# switch_v2.net
KiCad netlist of a schematic drawn in EAGLE
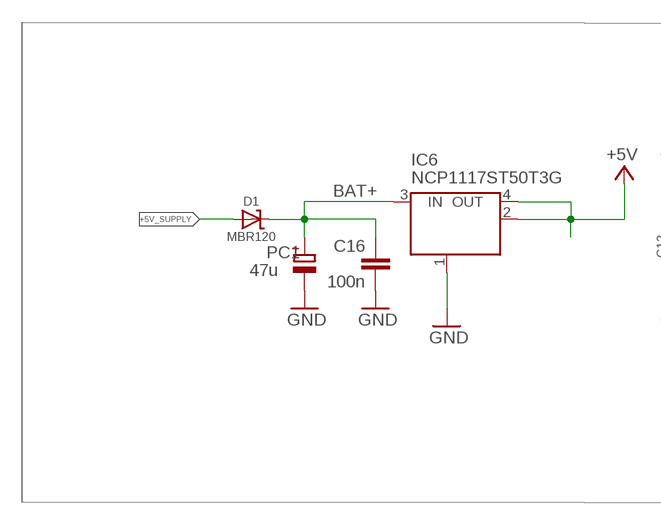
[diagram p0: schematic, sheet 1, part 1 of 2]
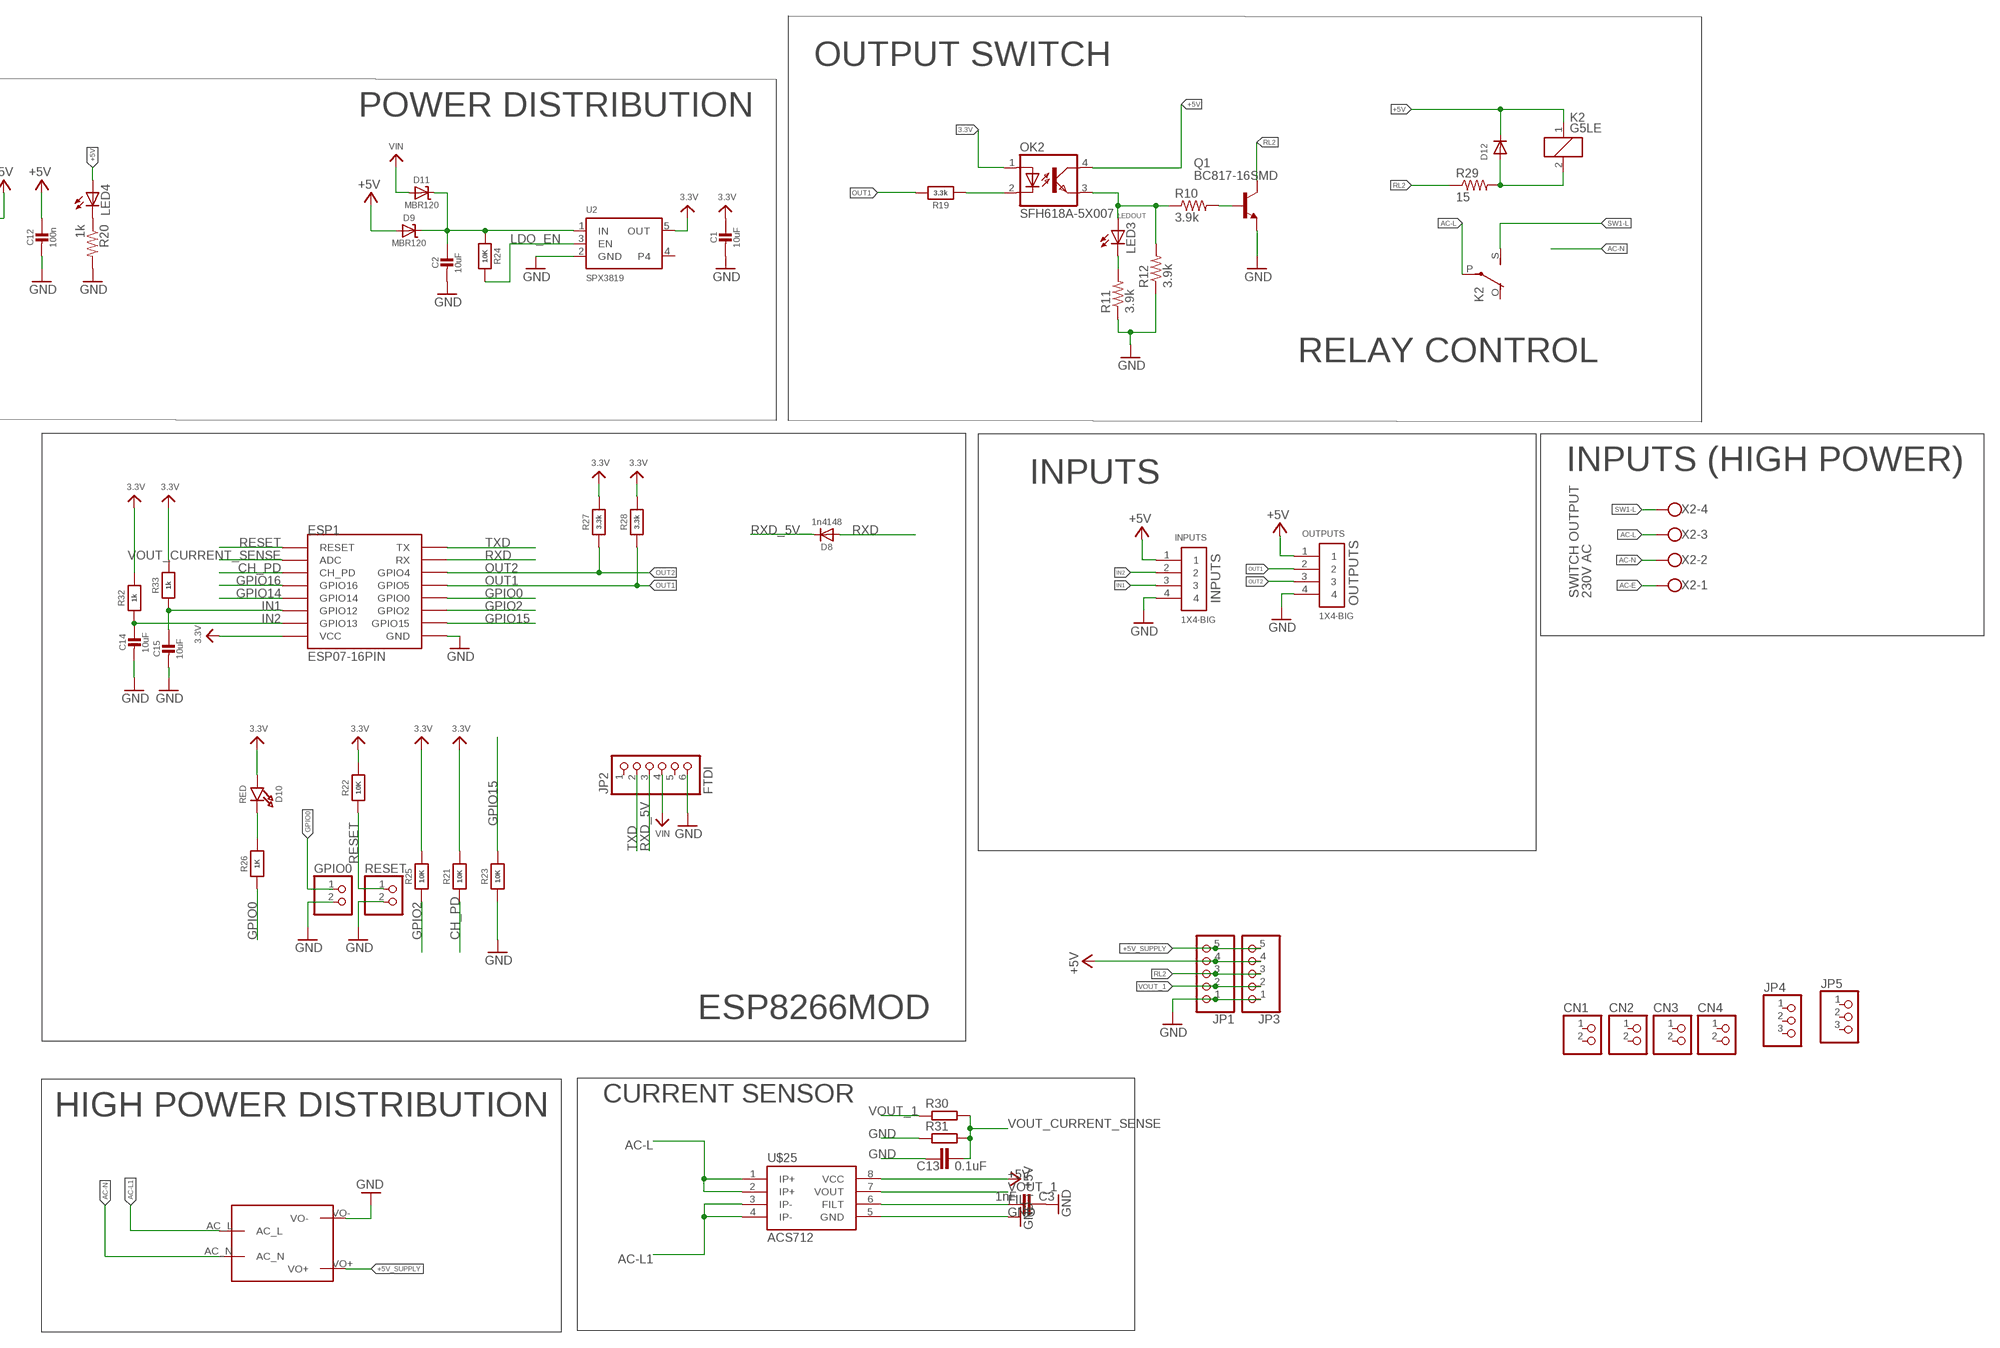
[diagram p1: schematic, sheet 1, part 2 of 2]

(export (version "E")
  (design (tool "Eeschema 10.0.6"))
  (components
    (comp (ref "C1")
      (value "10uF")
      (footprint "eagle-import:_0603")
      (libsource (lib "eagle-import") (part "CAP_CERAMIC_0603"))
    )
    (comp (ref "C2")
      (value "10uF")
      (footprint "eagle-import:_0603")
      (libsource (lib "eagle-import") (part "CAP_CERAMIC_0603"))
    )
    (comp (ref "C3")
      (value "1nF")
      (footprint "eagle-import:C0603-ROUND")
      (libsource (lib "eagle-import") (part "C-EU0603-RND"))
    )
    (comp (ref "C12")
      (value "100n")
      (footprint "eagle-import:_0603")
      (libsource (lib "eagle-import") (part "CAP_CERAMIC_0603"))
    )
    (comp (ref "C13")
      (value "0.1uF")
      (footprint "eagle-import:C0603-ROUND")
      (libsource (lib "eagle-import") (part "C-EU0603-RND"))
    )
    (comp (ref "C14")
      (value "10uF")
      (footprint "eagle-import:_0603")
      (libsource (lib "eagle-import") (part "CAP_CERAMIC_0603"))
    )
    (comp (ref "C15")
      (value "10uF")
      (footprint "eagle-import:_0603")
      (libsource (lib "eagle-import") (part "CAP_CERAMIC_0603"))
    )
    (comp (ref "C16")
      (value "100n")
      (footprint "eagle-import:C0603-ROUND")
      (libsource (lib "eagle-import") (part "C-EU0603-RND"))
    )
    (comp (ref "CN1")
      (value "PINHD-1X2")
      (footprint "eagle-import:1X02")
      (libsource (lib "eagle-import") (part "PINHD-1X2"))
    )
    (comp (ref "CN2")
      (value "PINHD-1X2")
      (footprint "eagle-import:1X02")
      (libsource (lib "eagle-import") (part "PINHD-1X2"))
    )
    (comp (ref "CN3")
      (value "PINHD-1X2")
      (footprint "eagle-import:1X02")
      (libsource (lib "eagle-import") (part "PINHD-1X2"))
    )
    (comp (ref "CN4")
      (value "PINHD-1X2")
      (footprint "eagle-import:1X02")
      (libsource (lib "eagle-import") (part "PINHD-1X2"))
    )
    (comp (ref "D1")
      (value "MBR120")
      (footprint "eagle-import:SOD-123")
      (libsource (lib "eagle-import") (part "DIODE-SCHOTTKYSOD-123"))
    )
    (comp (ref "D8")
      (value "1n4148")
      (footprint "eagle-import:SOD-323")
      (libsource (lib "eagle-import") (part "DIODESOD-323"))
    )
    (comp (ref "D9")
      (value "MBR120")
      (footprint "eagle-import:SOD-123")
      (libsource (lib "eagle-import") (part "DIODE-SCHOTTKYSOD-123"))
    )
    (comp (ref "D10")
      (value "RED")
      (footprint "eagle-import:CHIPLED_0603_NOOUTLINE")
      (libsource (lib "eagle-import") (part "LED0603_NOOUTLINE"))
    )
    (comp (ref "D11")
      (value "MBR120")
      (footprint "eagle-import:SOD-123")
      (libsource (lib "eagle-import") (part "DIODE-SCHOTTKYSOD-123"))
    )
    (comp (ref "D12")
      (value "DIODESOD-523")
      (footprint "eagle-import:SOD-523")
      (libsource (lib "eagle-import") (part "DIODESOD-523"))
    )
    (comp (ref "ESP1")
      (value "ESP07-16PIN")
      (footprint "eagle-import:ESP07-16PIN")
      (libsource (lib "eagle-import") (part "ESP07-16PIN"))
    )
    (comp (ref "GPIO0")
      (value "PINHD-1X2")
      (footprint "eagle-import:1X02")
      (libsource (lib "eagle-import") (part "PINHD-1X2"))
    )
    (comp (ref "IC6")
      (value "NCP1117ST50T3G")
      (footprint "eagle-import:SOT223")
      (libsource (lib "eagle-import") (part "MC33269ST-3.3T3"))
    )
    (comp (ref "INPUTS")
      (value "1X4-BIG")
      (footprint "eagle-import:1X04-BIG")
      (libsource (lib "eagle-import") (part "1X4-BIG"))
    )
    (comp (ref "JP1")
      (value "PINHD-1X5")
      (footprint "eagle-import:1X05")
      (libsource (lib "eagle-import") (part "PINHD-1X5"))
    )
    (comp (ref "JP2")
      (value "FTDI")
      (footprint "eagle-import:1X06_ROUND_70")
      (libsource (lib "eagle-import") (part "HEADER-1X670MIL"))
    )
    (comp (ref "JP3")
      (value "PINHD-1X5")
      (footprint "eagle-import:1X05")
      (libsource (lib "eagle-import") (part "PINHD-1X5"))
    )
    (comp (ref "JP4")
      (value "PINHD-1X3")
      (footprint "eagle-import:1X03")
      (libsource (lib "eagle-import") (part "PINHD-1X3"))
    )
    (comp (ref "JP5")
      (value "PINHD-1X3")
      (footprint "eagle-import:1X03")
      (libsource (lib "eagle-import") (part "PINHD-1X3"))
    )
    (comp (ref "K2")
      (value "G5LE")
      (footprint "eagle-import:G5LE")
      (libsource (lib "eagle-import") (part "G5LE"))
    )
    (comp (ref "LED3")
      (value "LEDCHIP-LED0603")
      (footprint "eagle-import:CHIP-LED0603")
      (libsource (lib "eagle-import") (part "LEDCHIP-LED0603"))
    )
    (comp (ref "LED4")
      (value "LEDCHIP-LED0603")
      (footprint "eagle-import:CHIP-LED0603")
      (libsource (lib "eagle-import") (part "LEDCHIP-LED0603"))
    )
    (comp (ref "OK2")
      (value "SFH618A-5X007")
      (footprint "eagle-import:SMD4-7")
      (libsource (lib "eagle-import") (part "SFH618?A-5X007"))
    )
    (comp (ref "OUTPUTS")
      (value "1X4-BIG")
      (footprint "eagle-import:1X04-BIG")
      (libsource (lib "eagle-import") (part "1X4-BIG"))
    )
    (comp (ref "PC1")
      (value "47u")
      (footprint "eagle-import:PANASONIC_D")
      (libsource (lib "eagle-import") (part "CPOL-EUD"))
    )
    (comp (ref "Q1")
      (value "BC817-16SMD")
      (footprint "eagle-import:SOT23-BEC")
      (libsource (lib "eagle-import") (part "BC817SMD-16"))
    )
    (comp (ref "R10")
      (value "3.9k")
      (footprint "eagle-import:R0603")
      (libsource (lib "eagle-import") (part "R-US_R0603"))
    )
    (comp (ref "R11")
      (value "3.9k")
      (footprint "eagle-import:R0603")
      (libsource (lib "eagle-import") (part "R-US_R0603"))
    )
    (comp (ref "R12")
      (value "3.9k")
      (footprint "eagle-import:R0603")
      (libsource (lib "eagle-import") (part "R-US_R0603"))
    )
    (comp (ref "R19")
      (value "3.3k")
      (footprint "eagle-import:_0603MP")
      (libsource (lib "eagle-import") (part "RESISTOR_0603MP"))
    )
    (comp (ref "R20")
      (value "1k")
      (footprint "eagle-import:R0603")
      (libsource (lib "eagle-import") (part "R-US_R0603"))
    )
    (comp (ref "R21")
      (value "10K")
      (footprint "eagle-import:0603-NO")
      (libsource (lib "eagle-import") (part "RESISTOR_0603_NOOUT"))
    )
    (comp (ref "R22")
      (value "10K")
      (footprint "eagle-import:0603-NO")
      (libsource (lib "eagle-import") (part "RESISTOR_0603_NOOUT"))
    )
    (comp (ref "R23")
      (value "10K")
      (footprint "eagle-import:0603-NO")
      (libsource (lib "eagle-import") (part "RESISTOR_0603_NOOUT"))
    )
    (comp (ref "R24")
      (value "10K")
      (footprint "eagle-import:0603-NO")
      (libsource (lib "eagle-import") (part "RESISTOR_0603_NOOUT"))
    )
    (comp (ref "R25")
      (value "10K")
      (footprint "eagle-import:0603-NO")
      (libsource (lib "eagle-import") (part "RESISTOR_0603_NOOUT"))
    )
    (comp (ref "R26")
      (value "1K")
      (footprint "eagle-import:0603-NO")
      (libsource (lib "eagle-import") (part "RESISTOR_0603_NOOUT"))
    )
    (comp (ref "R27")
      (value "3.3k")
      (footprint "eagle-import:_0603")
      (libsource (lib "eagle-import") (part "RESISTOR_0603"))
    )
    (comp (ref "R28")
      (value "3.3k")
      (footprint "eagle-import:_0603")
      (libsource (lib "eagle-import") (part "RESISTOR_0603"))
    )
    (comp (ref "R29")
      (value "15")
      (footprint "eagle-import:R0603")
      (libsource (lib "eagle-import") (part "R-US_R0603"))
    )
    (comp (ref "R30")
      (value "R-EU_R0603")
      (footprint "eagle-import:R0603")
      (libsource (lib "eagle-import") (part "R-EU_R0603"))
    )
    (comp (ref "R31")
      (value "R-EU_R0603")
      (footprint "eagle-import:R0603")
      (libsource (lib "eagle-import") (part "R-EU_R0603"))
    )
    (comp (ref "R32")
      (value "1k")
      (footprint "eagle-import:_0603")
      (libsource (lib "eagle-import") (part "RESISTOR_0603"))
    )
    (comp (ref "R33")
      (value "1k")
      (footprint "eagle-import:_0603")
      (libsource (lib "eagle-import") (part "RESISTOR_0603"))
    )
    (comp (ref "RESET")
      (value "PINHD-1X2")
      (footprint "eagle-import:1X02")
      (libsource (lib "eagle-import") (part "PINHD-1X2"))
    )
    (comp (ref "U$24")
      (value "MAINS_CONVERTERS")
      (footprint "eagle-import:HLK-PM01")
      (libsource (lib "eagle-import") (part "MAINS_CONVERTERS"))
    )
    (comp (ref "U$25")
      (value "ACS712")
      (footprint "eagle-import:SO08")
      (libsource (lib "eagle-import") (part "ACS712"))
    )
    (comp (ref "U2")
      (value "SPX3819")
      (footprint "eagle-import:SOT23-5")
      (libsource (lib "eagle-import") (part "VREG_SOT23-5"))
    )
    (comp (ref "X2")
      (value "W237-4")
      (footprint "eagle-import:W237-4")
      (libsource (lib "eagle-import") (part "W237-4"))
    )
  )
  (nets
    (net (code "1") (name "+5V") (class "Default")
      (node (ref "C12") (pin "1") (pinfunction "1_1") (pintype "passive"))
      (node (ref "D12") (pin "K") (pinfunction "C_K") (pintype "passive"))
      (node (ref "D9") (pin "A") (pinfunction "A_A") (pintype "passive"))
      (node (ref "IC6") (pin "2") (pinfunction "OUT_2") (pintype "passive"))
      (node (ref "IC6") (pin "4") (pinfunction "OUT_4") (pintype "passive"))
      (node (ref "INPUTS") (pin "1") (pinfunction "1_1") (pintype "bidirectional"))
      (node (ref "JP1") (pin "4") (pinfunction "4_4") (pintype "passive"))
      (node (ref "JP3") (pin "4") (pinfunction "4_4") (pintype "passive"))
      (node (ref "K2") (pin "1") (pinfunction "1_1") (pintype "passive"))
      (node (ref "LED4") (pin "A") (pinfunction "A_A") (pintype "passive"))
      (node (ref "OK2") (pin "4") (pinfunction "COL_4") (pintype "passive"))
      (node (ref "OUTPUTS") (pin "1") (pinfunction "1_1") (pintype "bidirectional"))
      (node (ref "U$25") (pin "8") (pinfunction "VCC_8") (pintype "bidirectional"))
    )
    (net (code "2") (name "+5V_SUPPLY") (class "Default")
      (node (ref "D1") (pin "A") (pinfunction "A_A") (pintype "passive"))
      (node (ref "JP1") (pin "5") (pinfunction "5_5") (pintype "passive"))
      (node (ref "JP3") (pin "5") (pinfunction "5_5") (pintype "passive"))
      (node (ref "U$24") (pin "VO+") (pinfunction "VO+_VO+") (pintype "output"))
    )
    (net (code "3") (name "/BAT+") (class "Default")
      (node (ref "C16") (pin "1") (pinfunction "1_1") (pintype "passive"))
      (node (ref "D1") (pin "C") (pinfunction "C_C") (pintype "passive"))
      (node (ref "IC6") (pin "3") (pinfunction "IN_3") (pintype "input"))
      (node (ref "PC1") (pin "+") (pinfunction "+_+") (pintype "passive"))
    )
    (net (code "4") (name "/CH_PD") (class "Default")
      (node (ref "ESP1") (pin "CH_PD") (pinfunction "CH_PD_CH_PD") (pintype "bidirectional"))
      (node (ref "R21") (pin "1") (pinfunction "1_1") (pintype "passive"))
    )
    (net (code "5") (name "/FILT") (class "Default")
      (node (ref "C3") (pin "2") (pinfunction "2_2") (pintype "passive"))
      (node (ref "U$25") (pin "6") (pinfunction "FILT_6") (pintype "bidirectional"))
    )
    (net (code "6") (name "/GPIO2") (class "Default")
      (node (ref "ESP1") (pin "GPIO2") (pinfunction "GPIO2_GPIO2") (pintype "bidirectional"))
      (node (ref "R25") (pin "1") (pinfunction "1_1") (pintype "passive"))
    )
    (net (code "7") (name "/GPIO14") (class "Default")
      (node (ref "ESP1") (pin "GPIO14") (pinfunction "GPIO14_GPIO14") (pintype "bidirectional"))
    )
    (net (code "8") (name "/GPIO15") (class "Default")
      (node (ref "ESP1") (pin "GPIO15") (pinfunction "GPIO15_GPIO15") (pintype "bidirectional"))
      (node (ref "R23") (pin "2") (pinfunction "2_2") (pintype "passive"))
    )
    (net (code "9") (name "/GPIO16") (class "Default")
      (node (ref "ESP1") (pin "GPIO16") (pinfunction "GPIO16_GPIO16") (pintype "bidirectional"))
    )
    (net (code "10") (name "/LDO_EN") (class "Default")
      (node (ref "R24") (pin "2") (pinfunction "2_2") (pintype "passive"))
      (node (ref "U2") (pin "3") (pinfunction "EN_3") (pintype "input"))
    )
    (net (code "11") (name "/LEDOUT") (class "Default")
      (node (ref "LED3") (pin "A") (pinfunction "A_A") (pintype "passive"))
      (node (ref "OK2") (pin "3") (pinfunction "EMIT_3") (pintype "passive"))
      (node (ref "R10") (pin "1") (pinfunction "1_1") (pintype "passive"))
      (node (ref "R12") (pin "2") (pinfunction "2_2") (pintype "passive"))
    )
    (net (code "12") (name "/RESET") (class "Default")
      (node (ref "ESP1") (pin "REST") (pinfunction "RESET_REST") (pintype "bidirectional"))
      (node (ref "R22") (pin "1") (pinfunction "1_1") (pintype "passive"))
      (node (ref "RESET") (pin "1") (pinfunction "1_1") (pintype "passive"))
    )
    (net (code "13") (name "/RXD") (class "Default")
      (node (ref "D8") (pin "A") (pinfunction "A_A") (pintype "passive"))
      (node (ref "ESP1") (pin "RX") (pinfunction "RX_RX") (pintype "bidirectional"))
    )
    (net (code "14") (name "/RXD_5V") (class "Default")
      (node (ref "D8") (pin "C") (pinfunction "C_C") (pintype "passive"))
      (node (ref "JP2") (pin "3") (pinfunction "3_3") (pintype "passive"))
    )
    (net (code "15") (name "/TXD") (class "Default")
      (node (ref "ESP1") (pin "TX") (pinfunction "TX_TX") (pintype "bidirectional"))
      (node (ref "JP2") (pin "2") (pinfunction "2_2") (pintype "passive"))
    )
    (net (code "16") (name "/VOUT_CURRENT_SENSE") (class "Default")
      (node (ref "C13") (pin "2") (pinfunction "2_2") (pintype "passive"))
      (node (ref "ESP1") (pin "ADC") (pinfunction "ADC_ADC") (pintype "bidirectional"))
      (node (ref "R30") (pin "2") (pinfunction "2_2") (pintype "passive"))
      (node (ref "R31") (pin "2") (pinfunction "2_2") (pintype "passive"))
    )
    (net (code "17") (name "3.3V") (class "Default")
      (node (ref "C1") (pin "1") (pinfunction "1_1") (pintype "passive"))
      (node (ref "D10") (pin "A") (pinfunction "A_A") (pintype "passive"))
      (node (ref "ESP1") (pin "VCC") (pinfunction "VCC_VCC") (pintype "bidirectional"))
      (node (ref "OK2") (pin "1") (pinfunction "A_1") (pintype "passive"))
      (node (ref "R21") (pin "2") (pinfunction "2_2") (pintype "passive"))
      (node (ref "R22") (pin "2") (pinfunction "2_2") (pintype "passive"))
      (node (ref "R25") (pin "2") (pinfunction "2_2") (pintype "passive"))
      (node (ref "R27") (pin "2") (pinfunction "2_2") (pintype "passive"))
      (node (ref "R28") (pin "2") (pinfunction "2_2") (pintype "passive"))
      (node (ref "R32") (pin "2") (pinfunction "2_2") (pintype "passive"))
      (node (ref "R33") (pin "2") (pinfunction "2_2") (pintype "passive"))
      (node (ref "U2") (pin "5") (pinfunction "OUT_5") (pintype "power_in"))
    )
    (net (code "18") (name "AC-E") (class "Default")
      (node (ref "X2") (pin "1") (pinfunction "KL_1") (pintype "passive"))
    )
    (net (code "19") (name "AC-L") (class "Default")
      (node (ref "K2") (pin "P") (pinfunction "P_P") (pintype "passive"))
      (node (ref "U$25") (pin "1") (pinfunction "IP+_1") (pintype "bidirectional"))
      (node (ref "U$25") (pin "2") (pinfunction "IP+_2") (pintype "bidirectional"))
      (node (ref "X2") (pin "3") (pinfunction "KL_3") (pintype "passive"))
    )
    (net (code "20") (name "AC-L1") (class "Default")
      (node (ref "U$24") (pin "AC_L") (pinfunction "AC_L_AC_L") (pintype "input"))
      (node (ref "U$25") (pin "3") (pinfunction "IP-_3") (pintype "bidirectional"))
      (node (ref "U$25") (pin "4") (pinfunction "IP-_4") (pintype "bidirectional"))
    )
    (net (code "21") (name "AC-N") (class "Default")
      (node (ref "U$24") (pin "AC_N") (pinfunction "AC_N_AC_N") (pintype "input"))
      (node (ref "X2") (pin "2") (pinfunction "KL_2") (pintype "passive"))
    )
    (net (code "22") (name "GND") (class "Default")
      (node (ref "C1") (pin "2") (pinfunction "2_2") (pintype "passive"))
      (node (ref "C12") (pin "2") (pinfunction "2_2") (pintype "passive"))
      (node (ref "C13") (pin "1") (pinfunction "1_1") (pintype "passive"))
      (node (ref "C14") (pin "2") (pinfunction "2_2") (pintype "passive"))
      (node (ref "C15") (pin "2") (pinfunction "2_2") (pintype "passive"))
      (node (ref "C16") (pin "2") (pinfunction "2_2") (pintype "passive"))
      (node (ref "C2") (pin "2") (pinfunction "2_2") (pintype "passive"))
      (node (ref "C3") (pin "1") (pinfunction "1_1") (pintype "passive"))
      (node (ref "ESP1") (pin "GND") (pinfunction "GND_GND") (pintype "bidirectional"))
      (node (ref "GPIO0") (pin "2") (pinfunction "2_2") (pintype "passive"))
      (node (ref "IC6") (pin "1") (pinfunction "GND/ADJ_1") (pintype "input"))
      (node (ref "INPUTS") (pin "4") (pinfunction "4_4") (pintype "bidirectional"))
      (node (ref "JP1") (pin "1") (pinfunction "1_1") (pintype "passive"))
      (node (ref "JP2") (pin "6") (pinfunction "6_6") (pintype "passive"))
      (node (ref "JP3") (pin "1") (pinfunction "1_1") (pintype "passive"))
      (node (ref "OUTPUTS") (pin "4") (pinfunction "4_4") (pintype "bidirectional"))
      (node (ref "PC1") (pin "-") (pinfunction "-_-") (pintype "passive"))
      (node (ref "Q1") (pin "E") (pinfunction "E_E") (pintype "passive"))
      (node (ref "R11") (pin "1") (pinfunction "1_1") (pintype "passive"))
      (node (ref "R12") (pin "1") (pinfunction "1_1") (pintype "passive"))
      (node (ref "R20") (pin "2") (pinfunction "2_2") (pintype "passive"))
      (node (ref "R23") (pin "1") (pinfunction "1_1") (pintype "passive"))
      (node (ref "R31") (pin "1") (pinfunction "1_1") (pintype "passive"))
      (node (ref "RESET") (pin "2") (pinfunction "2_2") (pintype "passive"))
      (node (ref "U$24") (pin "VO-") (pinfunction "VO-_VO-") (pintype "output"))
      (node (ref "U$25") (pin "5") (pinfunction "GND_5") (pintype "bidirectional"))
      (node (ref "U2") (pin "2") (pinfunction "GND_2") (pintype "power_in"))
    )
    (net (code "23") (name "GPIO0") (class "Default")
      (node (ref "ESP1") (pin "GPIO0") (pinfunction "GPIO0_GPIO0") (pintype "bidirectional"))
      (node (ref "GPIO0") (pin "1") (pinfunction "1_1") (pintype "passive"))
      (node (ref "R26") (pin "1") (pinfunction "1_1") (pintype "passive"))
    )
    (net (code "24") (name "IN1") (class "Default")
      (node (ref "C15") (pin "1") (pinfunction "1_1") (pintype "passive"))
      (node (ref "ESP1") (pin "GPIO12") (pinfunction "GPIO12_GPIO12") (pintype "bidirectional"))
      (node (ref "INPUTS") (pin "3") (pinfunction "3_3") (pintype "bidirectional"))
      (node (ref "R33") (pin "1") (pinfunction "1_1") (pintype "passive"))
    )
    (net (code "25") (name "IN2") (class "Default")
      (node (ref "C14") (pin "1") (pinfunction "1_1") (pintype "passive"))
      (node (ref "ESP1") (pin "GPIO13") (pinfunction "GPIO13_GPIO13") (pintype "bidirectional"))
      (node (ref "INPUTS") (pin "2") (pinfunction "2_2") (pintype "bidirectional"))
      (node (ref "R32") (pin "1") (pinfunction "1_1") (pintype "passive"))
    )
    (net (code "26") (name "Net-(D10-PadC)") (class "Default")
      (node (ref "D10") (pin "C") (pinfunction "C_C") (pintype "passive"))
      (node (ref "R26") (pin "2") (pinfunction "2_2") (pintype "passive"))
    )
    (net (code "27") (name "Net-(D12-PadA)") (class "Default")
      (node (ref "D12") (pin "A") (pinfunction "A_A") (pintype "passive"))
      (node (ref "K2") (pin "2") (pinfunction "2_2") (pintype "passive"))
      (node (ref "R29") (pin "2") (pinfunction "2_2") (pintype "passive"))
    )
    (net (code "28") (name "Net-(LED3-PadC)") (class "Default")
      (node (ref "LED3") (pin "C") (pinfunction "C_C") (pintype "passive"))
      (node (ref "R11") (pin "2") (pinfunction "2_2") (pintype "passive"))
    )
    (net (code "29") (name "Net-(LED4-PadC)") (class "Default")
      (node (ref "LED4") (pin "C") (pinfunction "C_C") (pintype "passive"))
      (node (ref "R20") (pin "1") (pinfunction "1_1") (pintype "passive"))
    )
    (net (code "30") (name "Net-(OK2-C)") (class "Default")
      (node (ref "OK2") (pin "2") (pinfunction "C_2") (pintype "passive"))
      (node (ref "R19") (pin "1") (pinfunction "1_1") (pintype "passive"))
    )
    (net (code "31") (name "Net-(Q1-PadB)") (class "Default")
      (node (ref "Q1") (pin "B") (pinfunction "B_B") (pintype "passive"))
      (node (ref "R10") (pin "2") (pinfunction "2_2") (pintype "passive"))
    )
    (net (code "32") (name "Net-(U2-IN)") (class "Default")
      (node (ref "C2") (pin "1") (pinfunction "1_1") (pintype "passive"))
      (node (ref "D11") (pin "C") (pinfunction "C_C") (pintype "passive"))
      (node (ref "D9") (pin "C") (pinfunction "C_C") (pintype "passive"))
      (node (ref "R24") (pin "1") (pinfunction "1_1") (pintype "passive"))
      (node (ref "U2") (pin "1") (pinfunction "IN_1") (pintype "power_in"))
    )
    (net (code "33") (name "OUT1") (class "Default")
      (node (ref "ESP1") (pin "GPIO5") (pinfunction "GPIO5_GPIO5") (pintype "bidirectional"))
      (node (ref "OUTPUTS") (pin "2") (pinfunction "2_2") (pintype "bidirectional"))
      (node (ref "R19") (pin "2") (pinfunction "2_2") (pintype "passive"))
      (node (ref "R28") (pin "1") (pinfunction "1_1") (pintype "passive"))
    )
    (net (code "34") (name "OUT2") (class "Default")
      (node (ref "ESP1") (pin "GPIO4") (pinfunction "GPIO4_GPIO4") (pintype "bidirectional"))
      (node (ref "OUTPUTS") (pin "3") (pinfunction "3_3") (pintype "bidirectional"))
      (node (ref "R27") (pin "1") (pinfunction "1_1") (pintype "passive"))
    )
    (net (code "35") (name "RL2") (class "Default")
      (node (ref "JP1") (pin "3") (pinfunction "3_3") (pintype "passive"))
      (node (ref "JP3") (pin "3") (pinfunction "3_3") (pintype "passive"))
      (node (ref "Q1") (pin "C") (pinfunction "C_C") (pintype "passive"))
      (node (ref "R29") (pin "1") (pinfunction "1_1") (pintype "passive"))
    )
    (net (code "36") (name "SW1-L") (class "Default")
      (node (ref "K2") (pin "S") (pinfunction "S_S") (pintype "passive"))
      (node (ref "X2") (pin "4") (pinfunction "KL_4") (pintype "passive"))
    )
    (net (code "37") (name "VIN") (class "Default")
      (node (ref "D11") (pin "A") (pinfunction "A_A") (pintype "passive"))
      (node (ref "JP2") (pin "4") (pinfunction "4_4") (pintype "passive"))
    )
    (net (code "38") (name "VOUT_1") (class "Default")
      (node (ref "JP1") (pin "2") (pinfunction "2_2") (pintype "passive"))
      (node (ref "JP3") (pin "2") (pinfunction "2_2") (pintype "passive"))
      (node (ref "R30") (pin "1") (pinfunction "1_1") (pintype "passive"))
      (node (ref "U$25") (pin "7") (pinfunction "VOUT_7") (pintype "bidirectional"))
    )
    (net (code "39") (name "unconnected-(CN1-Pad1)") (class "Default")
      (node (ref "CN1") (pin "1") (pinfunction "1_1") (pintype "passive"))
    )
    (net (code "40") (name "unconnected-(CN1-Pad2)") (class "Default")
      (node (ref "CN1") (pin "2") (pinfunction "2_2") (pintype "passive"))
    )
    (net (code "41") (name "unconnected-(CN2-Pad1)") (class "Default")
      (node (ref "CN2") (pin "1") (pinfunction "1_1") (pintype "passive"))
    )
    (net (code "42") (name "unconnected-(CN2-Pad2)") (class "Default")
      (node (ref "CN2") (pin "2") (pinfunction "2_2") (pintype "passive"))
    )
    (net (code "43") (name "unconnected-(CN3-Pad1)") (class "Default")
      (node (ref "CN3") (pin "1") (pinfunction "1_1") (pintype "passive"))
    )
    (net (code "44") (name "unconnected-(CN3-Pad2)") (class "Default")
      (node (ref "CN3") (pin "2") (pinfunction "2_2") (pintype "passive"))
    )
    (net (code "45") (name "unconnected-(CN4-Pad1)") (class "Default")
      (node (ref "CN4") (pin "1") (pinfunction "1_1") (pintype "passive"))
    )
    (net (code "46") (name "unconnected-(CN4-Pad2)") (class "Default")
      (node (ref "CN4") (pin "2") (pinfunction "2_2") (pintype "passive"))
    )
    (net (code "47") (name "unconnected-(JP2-Pad1)") (class "Default")
      (node (ref "JP2") (pin "1") (pinfunction "1_1") (pintype "passive"))
    )
    (net (code "48") (name "unconnected-(JP2-Pad5)") (class "Default")
      (node (ref "JP2") (pin "5") (pinfunction "5_5") (pintype "passive"))
    )
    (net (code "49") (name "unconnected-(JP4-Pad1)") (class "Default")
      (node (ref "JP4") (pin "1") (pinfunction "1_1") (pintype "passive"))
    )
    (net (code "50") (name "unconnected-(JP4-Pad2)") (class "Default")
      (node (ref "JP4") (pin "2") (pinfunction "2_2") (pintype "passive"))
    )
    (net (code "51") (name "unconnected-(JP4-Pad3)") (class "Default")
      (node (ref "JP4") (pin "3") (pinfunction "3_3") (pintype "passive"))
    )
    (net (code "52") (name "unconnected-(JP5-Pad1)") (class "Default")
      (node (ref "JP5") (pin "1") (pinfunction "1_1") (pintype "passive"))
    )
    (net (code "53") (name "unconnected-(JP5-Pad2)") (class "Default")
      (node (ref "JP5") (pin "2") (pinfunction "2_2") (pintype "passive"))
    )
    (net (code "54") (name "unconnected-(JP5-Pad3)") (class "Default")
      (node (ref "JP5") (pin "3") (pinfunction "3_3") (pintype "passive"))
    )
    (net (code "55") (name "unconnected-(K2-PadO)") (class "Default")
      (node (ref "K2") (pin "O") (pinfunction "O_O") (pintype "passive"))
    )
    (net (code "56") (name "unconnected-(U2-P4-Pad4)") (class "Default")
      (node (ref "U2") (pin "4") (pinfunction "P4_4") (pintype "bidirectional"))
    )
  )
)
